# Microcontroller.net
KiCad netlist of a schematic drawn in Altium Designer
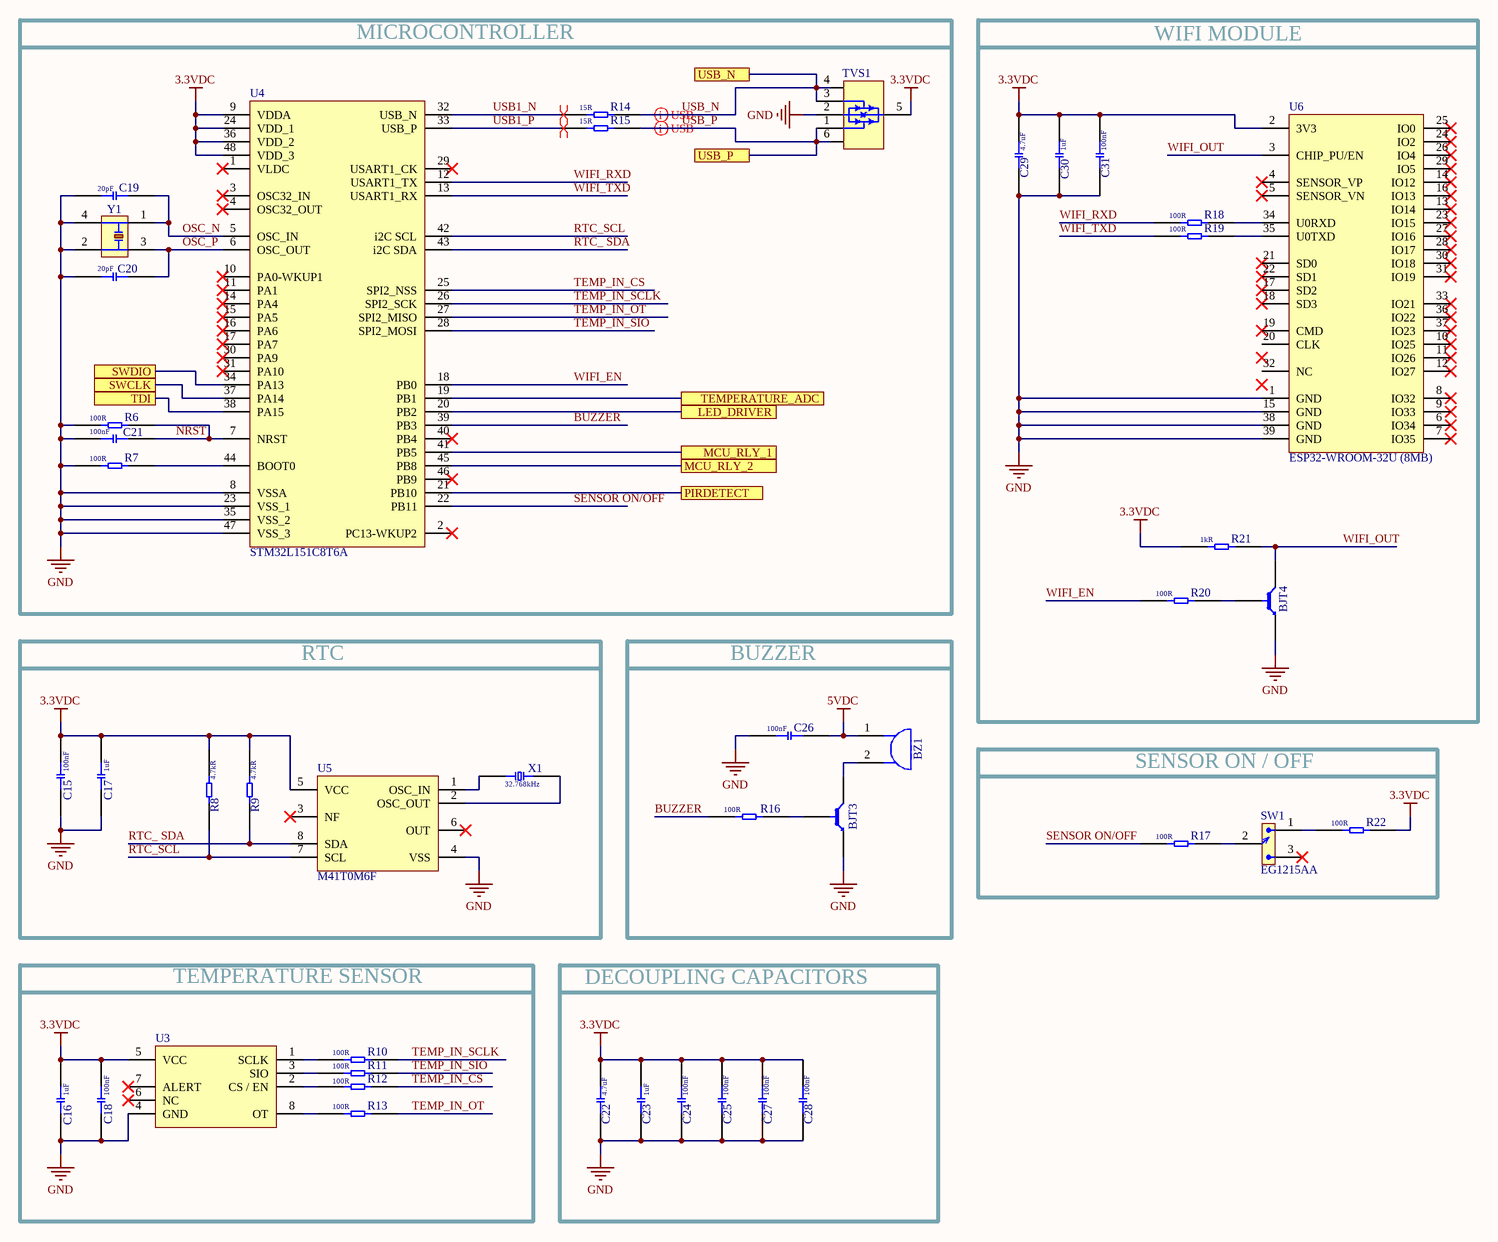
[diagram p0: Microcontroller.SchDoc]

(export (version "E")
  (design (tool "Eeschema 10.0.6"))
  (components
    (comp (ref "BJT3")
      (value "MMBT3904-7-F")
      (footprint "SOT-23F")
      (description "TRANS NPN 40V 0.2A SMD SOT23-3")
      (fields (field (name "MANUFACTURER") "Diodes Zetex") (field (name "DESIGNED BY") "M.C"))
      (libsource (lib "HedefPro_Library") (part "MMBT3904-7-F"))
    )
    (comp (ref "BJT4")
      (value "MMBT3904-7-F")
      (footprint "SOT-23F")
      (description "TRANS NPN 40V 0.2A SMD SOT23-3")
      (fields (field (name "MANUFACTURER") "Diodes Zetex") (field (name "DESIGNED BY") "M.C"))
      (libsource (lib "HedefPro_Library") (part "MMBT3904-7-F"))
    )
    (comp (ref "BZ1")
      (value "CMI-1295IC-0585T")
      (footprint "CMI-1295IC")
      (description "Buzzers Indicator, Internally Driven Magnetic 5 V 30mA 2.4kHz 85dB @ 5V, 10cm Through Hole PC Pins")
      (fields (field (name "MANUFACTURER") "CUI Devices") (field (name "DESIGNED BY") "M.C"))
      (libsource (lib "HedefPro_Library") (part "CMI-1295IC-0585T"))
    )
    (comp (ref "C15")
      (value "C0603C104K5RACTU")
      (footprint "CAP_0603")
      (description "Multilayer Ceramic Capacitors (MLCC) - SMD/SMT 50volts 0.1uF X7R 10%")
      (fields
        (field (name "MANUFACTURER") "KEMET")
        (field (name "TOLERANCE") "10%")
        (field (name "CAPACITANCE") "100nF")
        (field (name "DESIGNED BY") "M.C")
      )
      (libsource (lib "HedefPro_Library") (part "CAP 100nF 0603"))
    )
    (comp (ref "C16")
      (value "CL21B105KBFNNNE")
      (footprint "CAP_0805")
      (fields
        (field (name "MANUFACTURER") "Samsung")
        (field (name "TOLERANCE") "10%")
        (field (name "VOLTAGE") "50V")
        (field (name "CAPACITANCE") "1uF")
        (field (name "DESIGNED BY") "M.C")
      )
      (libsource (lib "HedefPro_Library") (part "CAP 1uF 0805"))
    )
    (comp (ref "C17")
      (value "CL21B105KBFNNNE")
      (footprint "CAP_0805")
      (fields
        (field (name "MANUFACTURER") "Samsung")
        (field (name "TOLERANCE") "10%")
        (field (name "VOLTAGE") "50V")
        (field (name "CAPACITANCE") "1uF")
        (field (name "DESIGNED BY") "M.C")
      )
      (libsource (lib "HedefPro_Library") (part "CAP 1uF 0805"))
    )
    (comp (ref "C18")
      (value "CL21B104KBCNNNC")
      (footprint "CAP_0805")
      (fields
        (field (name "MANUFACTURER") "Samsung")
        (field (name "TOLERANCE") "10%")
        (field (name "VOLTAGE") "50V")
        (field (name "CAPACITANCE") "100nF")
        (field (name "DESIGNED BY") "M.C")
      )
      (libsource (lib "HedefPro_Library") (part "CAP 100nF 0805"))
    )
    (comp (ref "C19")
      (value "CL10C200JB8NNNC")
      (footprint "CAP_0603")
      (fields
        (field (name "MANUFACTURER") "Samsung")
        (field (name "TOLERANCE") "5%")
        (field (name "VOLTAGE") "50V")
        (field (name "CAPACITANCE") "20pF")
        (field (name "DESIGNED BY") "M.C")
      )
      (libsource (lib "HedefPro_Library") (part "CAP 20pF 0805"))
    )
    (comp (ref "C20")
      (value "CL10C200JB8NNNC")
      (footprint "CAP_0603")
      (fields
        (field (name "MANUFACTURER") "Samsung")
        (field (name "TOLERANCE") "5%")
        (field (name "VOLTAGE") "50V")
        (field (name "CAPACITANCE") "20pF")
        (field (name "DESIGNED BY") "M.C")
      )
      (libsource (lib "HedefPro_Library") (part "CAP 20pF 0805"))
    )
    (comp (ref "C21")
      (value "CL21B104KBCNNNC")
      (footprint "CAP_0805")
      (fields
        (field (name "MANUFACTURER") "Samsung")
        (field (name "TOLERANCE") "10%")
        (field (name "VOLTAGE") "50V")
        (field (name "CAPACITANCE") "100nF")
        (field (name "DESIGNED BY") "M.C")
      )
      (libsource (lib "HedefPro_Library") (part "CAP 100nF 0805"))
    )
    (comp (ref "C22")
      (value "CL21A475KAQNNNE")
      (footprint "CAP_0805")
      (fields
        (field (name "MANUFACTURER") "Samsung")
        (field (name "TOLERANCE") "10%")
        (field (name "CAPACITANCE") "4.7uF")
        (field (name "DESIGNED BY") "M.C")
      )
      (libsource (lib "HedefPro_Library") (part "CAP 4.7uF 0805"))
    )
    (comp (ref "C23")
      (value "CL21B105KBFNNNE")
      (footprint "CAP_0805")
      (fields
        (field (name "MANUFACTURER") "Samsung")
        (field (name "TOLERANCE") "10%")
        (field (name "VOLTAGE") "50V")
        (field (name "CAPACITANCE") "1uF")
        (field (name "DESIGNED BY") "M.C")
      )
      (libsource (lib "HedefPro_Library") (part "CAP 1uF 0805"))
    )
    (comp (ref "C24")
      (value "CL21B104KBCNNNC")
      (footprint "CAP_0805")
      (fields
        (field (name "MANUFACTURER") "Samsung")
        (field (name "TOLERANCE") "10%")
        (field (name "VOLTAGE") "50V")
        (field (name "CAPACITANCE") "100nF")
        (field (name "DESIGNED BY") "M.C")
      )
      (libsource (lib "HedefPro_Library") (part "CAP 100nF 0805"))
    )
    (comp (ref "C25")
      (value "CL21B104KBCNNNC")
      (footprint "CAP_0805")
      (fields
        (field (name "MANUFACTURER") "Samsung")
        (field (name "TOLERANCE") "10%")
        (field (name "VOLTAGE") "50V")
        (field (name "CAPACITANCE") "100nF")
        (field (name "DESIGNED BY") "M.C")
      )
      (libsource (lib "HedefPro_Library") (part "CAP 100nF 0805"))
    )
    (comp (ref "C26")
      (value "ALA7DF471CF450")
      (footprint "CAP_0603")
      (description "CAP CER 100nF %10 0603 SMD")
      (fields
        (field (name "MANUFACTURER") "KEMET")
        (field (name "CAPATICANTE") "100nF")
        (field (name "DESIGNED BY") "M.C")
      )
      (libsource (lib "HedefPro_Library") (part "CAP 100nf 0603_1"))
    )
    (comp (ref "C27")
      (value "CL21B104KBCNNNC")
      (footprint "CAP_0805")
      (fields
        (field (name "MANUFACTURER") "Samsung")
        (field (name "TOLERANCE") "10%")
        (field (name "VOLTAGE") "50V")
        (field (name "CAPACITANCE") "100nF")
        (field (name "DESIGNED BY") "M.C")
      )
      (libsource (lib "HedefPro_Library") (part "CAP 100nF 0805"))
    )
    (comp (ref "C28")
      (value "CL21B104KBCNNNC")
      (footprint "CAP_0805")
      (fields
        (field (name "MANUFACTURER") "Samsung")
        (field (name "TOLERANCE") "10%")
        (field (name "VOLTAGE") "50V")
        (field (name "CAPACITANCE") "100nF")
        (field (name "DESIGNED BY") "M.C")
      )
      (libsource (lib "HedefPro_Library") (part "CAP 100nF 0805"))
    )
    (comp (ref "C29")
      (value "CL21A475KAQNNNE")
      (footprint "CAP_0805")
      (fields
        (field (name "MANUFACTURER") "Samsung")
        (field (name "TOLERANCE") "10%")
        (field (name "CAPACITANCE") "4.7uF")
        (field (name "DESIGNED BY") "M.C")
      )
      (libsource (lib "HedefPro_Library") (part "CAP 4.7uF 0805"))
    )
    (comp (ref "C30")
      (value "CL21B105KBFNNNE")
      (footprint "CAP_0805")
      (fields
        (field (name "MANUFACTURER") "Samsung")
        (field (name "TOLERANCE") "10%")
        (field (name "VOLTAGE") "50V")
        (field (name "CAPACITANCE") "1uF")
        (field (name "DESIGNED BY") "M.C")
      )
      (libsource (lib "HedefPro_Library") (part "CAP 1uF 0805"))
    )
    (comp (ref "C31")
      (value "CL21B104KBCNNNC")
      (footprint "CAP_0805")
      (fields
        (field (name "MANUFACTURER") "Samsung")
        (field (name "TOLERANCE") "10%")
        (field (name "VOLTAGE") "50V")
        (field (name "CAPACITANCE") "100nF")
        (field (name "DESIGNED BY") "M.C")
      )
      (libsource (lib "HedefPro_Library") (part "CAP 100nF 0805"))
    )
    (comp (ref "R6")
      (value "RC0603JR-07100RL")
      (footprint "RES_0603")
      (description "Res Thick Film 0603 100 Ohm 5% 0.1W(1/10W) ±100ppm/C Molded SMD Paper T/R")
      (fields
        (field (name "MANUFACTURER") "Yageo")
        (field (name "TOLERANCE") "5%")
        (field (name "RESISTANCE") "100R")
        (field (name "DESIGNED BY") "M.C")
      )
      (libsource (lib "HedefPro_Library") (part "RES 100R OHM 0603"))
    )
    (comp (ref "R7")
      (value "RC0603JR-07100RL")
      (footprint "RES_0603")
      (description "Res Thick Film 0603 100 Ohm 5% 0.1W(1/10W) ±100ppm/C Molded SMD Paper T/R")
      (fields
        (field (name "MANUFACTURER") "Yageo")
        (field (name "TOLERANCE") "5%")
        (field (name "RESISTANCE") "100R")
        (field (name "DESIGNED BY") "M.C")
      )
      (libsource (lib "HedefPro_Library") (part "RES 100R OHM 0603"))
    )
    (comp (ref "R8")
      (value "RC0603JR-074K7L")
      (footprint "RES_0603")
      (description "Res Thick Film 0603 4.7K Ohm 5% 0.1W(1/10W) ±100ppm/C Molded SMD Paper T/R")
      (fields
        (field (name "MANUFACTURER") "Yageo")
        (field (name "TOLERANCE") "5%")
        (field (name "RESISTANCE") "4.7kR")
        (field (name "DESIGNED BY") "M.C")
      )
      (libsource (lib "HedefPro_Library") (part "RES 4.7kR OHM 0603"))
    )
    (comp (ref "R9")
      (value "RC0603JR-074K7L")
      (footprint "RES_0603")
      (description "Res Thick Film 0603 4.7K Ohm 5% 0.1W(1/10W) ±100ppm/C Molded SMD Paper T/R")
      (fields
        (field (name "MANUFACTURER") "Yageo")
        (field (name "TOLERANCE") "5%")
        (field (name "RESISTANCE") "4.7kR")
        (field (name "DESIGNED BY") "M.C")
      )
      (libsource (lib "HedefPro_Library") (part "RES 4.7kR OHM 0603"))
    )
    (comp (ref "R10")
      (value "RC0603JR-07100RL")
      (footprint "RES_0603")
      (description "Res Thick Film 0603 100 Ohm 5% 0.1W(1/10W) ±100ppm/C Molded SMD Paper T/R")
      (fields
        (field (name "MANUFACTURER") "Yageo")
        (field (name "TOLERANCE") "5%")
        (field (name "RESISTANCE") "100R")
        (field (name "DESIGNED BY") "M.C")
      )
      (libsource (lib "HedefPro_Library") (part "RES 100R OHM 0603"))
    )
    (comp (ref "R11")
      (value "RC0603JR-07100RL")
      (footprint "RES_0603")
      (description "Res Thick Film 0603 100 Ohm 5% 0.1W(1/10W) ±100ppm/C Molded SMD Paper T/R")
      (fields
        (field (name "MANUFACTURER") "Yageo")
        (field (name "TOLERANCE") "5%")
        (field (name "RESISTANCE") "100R")
        (field (name "DESIGNED BY") "M.C")
      )
      (libsource (lib "HedefPro_Library") (part "RES 100R OHM 0603"))
    )
    (comp (ref "R12")
      (value "RC0603JR-07100RL")
      (footprint "RES_0603")
      (description "Res Thick Film 0603 100 Ohm 5% 0.1W(1/10W) ±100ppm/C Molded SMD Paper T/R")
      (fields
        (field (name "MANUFACTURER") "Yageo")
        (field (name "TOLERANCE") "5%")
        (field (name "RESISTANCE") "100R")
        (field (name "DESIGNED BY") "M.C")
      )
      (libsource (lib "HedefPro_Library") (part "RES 100R OHM 0603"))
    )
    (comp (ref "R13")
      (value "RC0603JR-07100RL")
      (footprint "RES_0603")
      (description "Res Thick Film 0603 100 Ohm 5% 0.1W(1/10W) ±100ppm/C Molded SMD Paper T/R")
      (fields
        (field (name "MANUFACTURER") "Yageo")
        (field (name "TOLERANCE") "5%")
        (field (name "RESISTANCE") "100R")
        (field (name "DESIGNED BY") "M.C")
      )
      (libsource (lib "HedefPro_Library") (part "RES 100R OHM 0603"))
    )
    (comp (ref "R14")
      (value "RC0603JR-0715RL")
      (footprint "RES_0603")
      (fields
        (field (name "MANUFACTURER") "Yageo")
        (field (name "TOLERANCE") "5%")
        (field (name "RESISTANCE") "15R")
        (field (name "DESIGNED BY") "M.C")
      )
      (libsource (lib "HedefPro_Library") (part "RES 15R OHM 0603"))
    )
    (comp (ref "R15")
      (value "RC0603JR-0715RL")
      (footprint "RES_0603")
      (fields
        (field (name "MANUFACTURER") "Yageo")
        (field (name "TOLERANCE") "5%")
        (field (name "RESISTANCE") "15R")
        (field (name "DESIGNED BY") "M.C")
      )
      (libsource (lib "HedefPro_Library") (part "RES 15R OHM 0603"))
    )
    (comp (ref "R16")
      (value "RC0603JR-07100RL")
      (footprint "RES_0603")
      (description "Res Thick Film 0603 100 Ohm 5% 0.1W(1/10W) ±100ppm/C Molded SMD Paper T/R")
      (fields
        (field (name "MANUFACTURER") "Yageo")
        (field (name "TOLERANCE") "5%")
        (field (name "RESISTANCE") "100R")
        (field (name "DESIGNED BY") "M.C")
      )
      (libsource (lib "HedefPro_Library") (part "RES 100R OHM 0603"))
    )
    (comp (ref "R17")
      (value "RC0603JR-07100RL")
      (footprint "RES_0603")
      (description "Res Thick Film 0603 100 Ohm 5% 0.1W(1/10W) ±100ppm/C Molded SMD Paper T/R")
      (fields
        (field (name "MANUFACTURER") "Yageo")
        (field (name "TOLERANCE") "5%")
        (field (name "RESISTANCE") "100R")
        (field (name "DESIGNED BY") "M.C")
      )
      (libsource (lib "HedefPro_Library") (part "RES 100R OHM 0603"))
    )
    (comp (ref "R18")
      (value "RC0603JR-07100RL")
      (footprint "RES_0603")
      (description "Res Thick Film 0603 100 Ohm 5% 0.1W(1/10W) ±100ppm/C Molded SMD Paper T/R")
      (fields
        (field (name "MANUFACTURER") "Yageo")
        (field (name "TOLERANCE") "5%")
        (field (name "RESISTANCE") "100R")
        (field (name "DESIGNED BY") "M.C")
      )
      (libsource (lib "HedefPro_Library") (part "RES 100R OHM 0603"))
    )
    (comp (ref "R19")
      (value "RC0603JR-07100RL")
      (footprint "RES_0603")
      (description "Res Thick Film 0603 100 Ohm 5% 0.1W(1/10W) ±100ppm/C Molded SMD Paper T/R")
      (fields
        (field (name "MANUFACTURER") "Yageo")
        (field (name "TOLERANCE") "5%")
        (field (name "RESISTANCE") "100R")
        (field (name "DESIGNED BY") "M.C")
      )
      (libsource (lib "HedefPro_Library") (part "RES 100R OHM 0603"))
    )
    (comp (ref "R20")
      (value "RC0603JR-07100RL")
      (footprint "RES_0603")
      (description "Res Thick Film 0603 100 Ohm 5% 0.1W(1/10W) ±100ppm/C Molded SMD Paper T/R")
      (fields
        (field (name "MANUFACTURER") "Yageo")
        (field (name "TOLERANCE") "5%")
        (field (name "RESISTANCE") "100R")
        (field (name "DESIGNED BY") "M.C")
      )
      (libsource (lib "HedefPro_Library") (part "RES 100R OHM 0603"))
    )
    (comp (ref "R21")
      (value "RC0603FR-101KL")
      (footprint "RES_0603")
      (description "Res Thick Film 0603 1K Ohm 1% 0.1W(1/10W) ±100ppm/C Pad SMD T/R")
      (fields
        (field (name "MANUFACTURER") "Yageo")
        (field (name "TOLERANCE") "1%")
        (field (name "RESISTANCE") "1kR")
        (field (name "DESIGNED BY") "M.C")
      )
      (libsource (lib "HedefPro_Library") (part "RES 1kR OHM 0603"))
    )
    (comp (ref "R22")
      (value "RC0603JR-07100RL")
      (footprint "RES_0603")
      (description "Res Thick Film 0603 100 Ohm 5% 0.1W(1/10W) ±100ppm/C Molded SMD Paper T/R")
      (fields
        (field (name "MANUFACTURER") "Yageo")
        (field (name "TOLERANCE") "5%")
        (field (name "RESISTANCE") "100R")
        (field (name "DESIGNED BY") "M.C")
      )
      (libsource (lib "HedefPro_Library") (part "RES 100R OHM 0603"))
    )
    (comp (ref "SW1")
      (value "EG1215AA")
      (footprint "EG1215AA")
      (description "Slide Switch, SPDT, 0.025A, 24V, SMD")
      (fields
        (field (name "MANUFACTURER") "E-Switch")
        (field (name "TOLERANCE") "4.95%")
        (field (name "DESIGNED BY") "M.C")
      )
      (libsource (lib "HedefPro_Library") (part "EG1215AA"))
    )
    (comp (ref "TVS1")
      (value "USBLC6-2SC6")
      (footprint "SOT23-6L")
      (description "TVS DIODE 5.25V 17V SOT23-6")
      (fields (field (name "MANUFACTURER") "STMicroelectronics") (field (name "DESIGNED BY") "M.C"))
      (libsource (lib "HedefPro_Library") (part "USBLC6-2SC6"))
    )
    (comp (ref "U3")
      (value "MAX6662MSA+T")
      (footprint "SOIC8")
      (description "Temp Sensor Digital Serial (3-Wire, SPI) 8-Pin SOIC N T/R")
      (fields (field (name "MANUFACTURER") "Maxim") (field (name "DESIGNED BY") "M.C"))
      (libsource (lib "HedefPro_Library") (part "MAX6662MSA+T"))
    )
    (comp (ref "U4")
      (value "STM32L151C8T6A")
      (footprint "LQFP48")
      (description "IC MCU 32BIT 64KB FLASH 48LQFP")
      (fields (field (name "MANUFACTURER") "STMicroelectronics") (field (name "DESIGNED BY") "M.C"))
      (libsource (lib "HedefPro_Library") (part "STM32L151C8T6A"))
    )
    (comp (ref "U5")
      (value "M41T0M6F")
      (footprint "SOIC8")
      (description "Real Time Clock Serial 8Byte 8-Pin SO N T/R")
      (fields (field (name "MANUFACTURER") "STMicroelectronics") (field (name "DESIGNED BY") "M.C"))
      (libsource (lib "HedefPro_Library") (part "M41T0M6F"))
    )
    (comp (ref "U6")
      (value "ESP32-WROOM-32U (8MB)")
      (footprint "ESP32_32U")
      (description "SMD Module, ESP32-D0WD, 64MBITS Spi Flash, Uart Mode, U.fl Antenna Connector")
      (fields
        (field (name "MANUFACTURER") "Espressif Systems")
        (field (name "TOLERANCE") "0.1%")
        (field (name "DESIGNED BY") "M.C")
      )
      (libsource (lib "HedefPro_Library") (part "ESP32-WROOM-32U (8MB)"))
    )
    (comp (ref "X1")
      (value "ABS05-32.768KHZ-T")
      (footprint "ABS05")
      (description "ABRACON - ABS05-32.768KHZ-T - Crystal, 32.768 kHz, SMD, 1.6mm x 1mm, 12.5 pF, 20 ppm, ABS05 Series")
      (fields
        (field (name "MANUFACTURER") "Abracon")
        (field (name "TOLERANCE") "20ppm")
        (field (name "FREQUENCY") "32.768kHz")
        (field (name "DESIGNED BY") "M.C")
      )
      (libsource (lib "HedefPro_Library") (part "ABS05-32.768KHZ-T"))
    )
    (comp (ref "Y1")
      (value "ECS-160-20-30B-TR")
      (footprint "SMD5032")
      (description "CRYSTAL 16.0000MHZ 20PF SMD")
      (fields
        (field (name "MANUFACTURER") "ECS International")
        (field (name "TOLERANCE") "50ppm")
        (field (name "DESIGNED BY") "M.C")
      )
      (libsource (lib "HedefPro_Library") (part "ECS-160-20-30B-TR"))
    )
  )
  (nets
    (net (code "1") (name "/BUZZER") (class "Default")
      (node (ref "R16") (pin "1") (pinfunction "1_1") (pintype "passive"))
      (node (ref "U4") (pin "39") (pinfunction "PB3_39") (pintype "passive"))
    )
    (net (code "2") (name "/LED_DRIVER") (class "Default")
      (node (ref "U4") (pin "20") (pinfunction "PB2_20") (pintype "passive"))
    )
    (net (code "3") (name "/MCU_RLY_1") (class "Default")
      (node (ref "U4") (pin "41") (pinfunction "PB5_41") (pintype "passive"))
    )
    (net (code "4") (name "/MCU_RLY_2") (class "Default")
      (node (ref "U4") (pin "45") (pinfunction "PB8_45") (pintype "passive"))
    )
    (net (code "5") (name "/NRST") (class "Default")
      (node (ref "C21") (pin "1") (pinfunction "1_1") (pintype "passive"))
      (node (ref "R6") (pin "2") (pinfunction "2_2") (pintype "passive"))
      (node (ref "U4") (pin "7") (pinfunction "NRST_7") (pintype "passive"))
    )
    (net (code "6") (name "/OSC_N") (class "Default")
      (node (ref "C19") (pin "2") (pinfunction "2_2") (pintype "passive"))
      (node (ref "U4") (pin "5") (pinfunction "OSC_IN_5") (pintype "passive"))
      (node (ref "Y1") (pin "1") (pinfunction "IN/OUT_1") (pintype "passive"))
    )
    (net (code "7") (name "/OSC_P") (class "Default")
      (node (ref "C20") (pin "2") (pinfunction "2_2") (pintype "passive"))
      (node (ref "U4") (pin "6") (pinfunction "OSC_OUT_6") (pintype "passive"))
      (node (ref "Y1") (pin "3") (pinfunction "OUT/IN_3") (pintype "passive"))
    )
    (net (code "8") (name "/PIRDETECT") (class "Default")
      (node (ref "U4") (pin "21") (pinfunction "PB10_21") (pintype "passive"))
    )
    (net (code "9") (name "/RTC_ SDA") (class "Default")
      (node (ref "R9") (pin "1") (pinfunction "1_1") (pintype "passive"))
      (node (ref "U4") (pin "43") (pinfunction "i2C_SDA_43") (pintype "passive"))
      (node (ref "U5") (pin "8") (pinfunction "SDA_8") (pintype "passive"))
    )
    (net (code "10") (name "/RTC_SCL") (class "Default")
      (node (ref "R8") (pin "1") (pinfunction "1_1") (pintype "passive"))
      (node (ref "U4") (pin "42") (pinfunction "i2C_SCL_42") (pintype "passive"))
      (node (ref "U5") (pin "7") (pinfunction "SCL_7") (pintype "passive"))
    )
    (net (code "11") (name "/SENSOR ON{slash}OFF") (class "Default")
      (node (ref "R17") (pin "1") (pinfunction "1_1") (pintype "passive"))
      (node (ref "U4") (pin "22") (pinfunction "PB11_22") (pintype "passive"))
    )
    (net (code "12") (name "/SWCLK") (class "Default")
      (node (ref "U4") (pin "37") (pinfunction "PA14_37") (pintype "passive"))
    )
    (net (code "13") (name "/SWDIO") (class "Default")
      (node (ref "U4") (pin "34") (pinfunction "PA13_34") (pintype "passive"))
    )
    (net (code "14") (name "/TDI") (class "Default")
      (node (ref "U4") (pin "38") (pinfunction "PA15_38") (pintype "passive"))
    )
    (net (code "15") (name "/TEMPERATURE_ADC") (class "Default")
      (node (ref "U4") (pin "19") (pinfunction "PB1_19") (pintype "passive"))
    )
    (net (code "16") (name "/TEMP_IN_CS") (class "Default")
      (node (ref "R12") (pin "1") (pinfunction "1_1") (pintype "passive"))
      (node (ref "U4") (pin "25") (pinfunction "SPI2_NSS_25") (pintype "passive"))
    )
    (net (code "17") (name "/TEMP_IN_OT") (class "Default")
      (node (ref "R13") (pin "1") (pinfunction "1_1") (pintype "passive"))
      (node (ref "U4") (pin "27") (pinfunction "SPI2_MISO_27") (pintype "passive"))
    )
    (net (code "18") (name "/TEMP_IN_SCLK") (class "Default")
      (node (ref "R10") (pin "1") (pinfunction "1_1") (pintype "passive"))
      (node (ref "U4") (pin "26") (pinfunction "SPI2_SCK_26") (pintype "passive"))
    )
    (net (code "19") (name "/TEMP_IN_SIO") (class "Default")
      (node (ref "R11") (pin "1") (pinfunction "1_1") (pintype "passive"))
      (node (ref "U4") (pin "28") (pinfunction "SPI2_MOSI_28") (pintype "passive"))
    )
    (net (code "20") (name "/USB1_N") (class "Default")
      (node (ref "R14") (pin "1") (pinfunction "1_1") (pintype "passive"))
      (node (ref "U4") (pin "32") (pinfunction "USB_N_32") (pintype "passive"))
    )
    (net (code "21") (name "/USB1_P") (class "Default")
      (node (ref "R15") (pin "1") (pinfunction "1_1") (pintype "passive"))
      (node (ref "U4") (pin "33") (pinfunction "USB_P_33") (pintype "passive"))
    )
    (net (code "22") (name "/USB_N") (class "Default")
      (node (ref "R14") (pin "2") (pinfunction "2_2") (pintype "passive"))
      (node (ref "TVS1") (pin "3") (pinfunction "D+in_3") (pintype "passive"))
      (node (ref "TVS1") (pin "4") (pinfunction "D+out_4") (pintype "passive"))
    )
    (net (code "23") (name "/USB_P") (class "Default")
      (node (ref "R15") (pin "2") (pinfunction "2_2") (pintype "passive"))
      (node (ref "TVS1") (pin "1") (pinfunction "D+in_1") (pintype "passive"))
      (node (ref "TVS1") (pin "6") (pinfunction "D-out_6") (pintype "passive"))
    )
    (net (code "24") (name "/WIFI_EN") (class "Default")
      (node (ref "R20") (pin "1") (pinfunction "1_1") (pintype "passive"))
      (node (ref "U4") (pin "18") (pinfunction "PB0_18") (pintype "passive"))
    )
    (net (code "25") (name "/WIFI_OUT") (class "Default")
      (node (ref "BJT4") (pin "3") (pinfunction "C_3") (pintype "passive"))
      (node (ref "R21") (pin "2") (pinfunction "2_2") (pintype "passive"))
      (node (ref "U6") (pin "3") (pinfunction "CHIP_PU/EN_3") (pintype "passive"))
    )
    (net (code "26") (name "/WIFI_RXD") (class "Default")
      (node (ref "R18") (pin "2") (pinfunction "2_2") (pintype "passive"))
      (node (ref "U4") (pin "12") (pinfunction "USART1_TX_12") (pintype "passive"))
    )
    (net (code "27") (name "/WIFI_TXD") (class "Default")
      (node (ref "R19") (pin "2") (pinfunction "2_2") (pintype "passive"))
      (node (ref "U4") (pin "13") (pinfunction "USART1_RX_13") (pintype "passive"))
    )
    (net (code "28") (name "3.3VDC") (class "Default")
      (node (ref "C15") (pin "2") (pinfunction "2_2") (pintype "passive"))
      (node (ref "C16") (pin "2") (pinfunction "2_2") (pintype "passive"))
      (node (ref "C17") (pin "2") (pinfunction "2_2") (pintype "passive"))
      (node (ref "C18") (pin "2") (pinfunction "2_2") (pintype "passive"))
      (node (ref "C22") (pin "2") (pinfunction "2_2") (pintype "passive"))
      (node (ref "C23") (pin "2") (pinfunction "2_2") (pintype "passive"))
      (node (ref "C24") (pin "2") (pinfunction "2_2") (pintype "passive"))
      (node (ref "C25") (pin "2") (pinfunction "2_2") (pintype "passive"))
      (node (ref "C27") (pin "2") (pinfunction "2_2") (pintype "passive"))
      (node (ref "C28") (pin "2") (pinfunction "2_2") (pintype "passive"))
      (node (ref "C29") (pin "2") (pinfunction "2_2") (pintype "passive"))
      (node (ref "C30") (pin "2") (pinfunction "2_2") (pintype "passive"))
      (node (ref "C31") (pin "2") (pinfunction "2_2") (pintype "passive"))
      (node (ref "R21") (pin "1") (pinfunction "1_1") (pintype "passive"))
      (node (ref "R22") (pin "2") (pinfunction "2_2") (pintype "passive"))
      (node (ref "R8") (pin "2") (pinfunction "2_2") (pintype "passive"))
      (node (ref "R9") (pin "2") (pinfunction "2_2") (pintype "passive"))
      (node (ref "TVS1") (pin "5") (pinfunction "VBUS_5") (pintype "passive"))
      (node (ref "U3") (pin "5") (pinfunction "VCC_5") (pintype "passive"))
      (node (ref "U4") (pin "24") (pinfunction "VDD_1_24") (pintype "passive"))
      (node (ref "U4") (pin "36") (pinfunction "VDD_2_36") (pintype "passive"))
      (node (ref "U4") (pin "48") (pinfunction "VDD_3_48") (pintype "passive"))
      (node (ref "U4") (pin "9") (pinfunction "VDDA_9") (pintype "passive"))
      (node (ref "U5") (pin "5") (pinfunction "VCC_5") (pintype "passive"))
      (node (ref "U6") (pin "2") (pinfunction "3V3_2") (pintype "passive"))
    )
    (net (code "29") (name "5VDC") (class "Default")
      (node (ref "BZ1") (pin "1") (pinfunction "1_1") (pintype "passive"))
      (node (ref "C26") (pin "2") (pinfunction "2_2") (pintype "passive"))
    )
    (net (code "30") (name "GND") (class "Default")
      (node (ref "BJT3") (pin "2") (pinfunction "E_2") (pintype "passive"))
      (node (ref "BJT4") (pin "2") (pinfunction "E_2") (pintype "passive"))
      (node (ref "C15") (pin "1") (pinfunction "1_1") (pintype "passive"))
      (node (ref "C16") (pin "1") (pinfunction "1_1") (pintype "passive"))
      (node (ref "C17") (pin "1") (pinfunction "1_1") (pintype "passive"))
      (node (ref "C18") (pin "1") (pinfunction "1_1") (pintype "passive"))
      (node (ref "C19") (pin "1") (pinfunction "1_1") (pintype "passive"))
      (node (ref "C20") (pin "1") (pinfunction "1_1") (pintype "passive"))
      (node (ref "C21") (pin "2") (pinfunction "2_2") (pintype "passive"))
      (node (ref "C22") (pin "1") (pinfunction "1_1") (pintype "passive"))
      (node (ref "C23") (pin "1") (pinfunction "1_1") (pintype "passive"))
      (node (ref "C24") (pin "1") (pinfunction "1_1") (pintype "passive"))
      (node (ref "C25") (pin "1") (pinfunction "1_1") (pintype "passive"))
      (node (ref "C26") (pin "1") (pinfunction "1_1") (pintype "passive"))
      (node (ref "C27") (pin "1") (pinfunction "1_1") (pintype "passive"))
      (node (ref "C28") (pin "1") (pinfunction "1_1") (pintype "passive"))
      (node (ref "C29") (pin "1") (pinfunction "1_1") (pintype "passive"))
      (node (ref "C30") (pin "1") (pinfunction "1_1") (pintype "passive"))
      (node (ref "C31") (pin "1") (pinfunction "1_1") (pintype "passive"))
      (node (ref "R6") (pin "1") (pinfunction "1_1") (pintype "passive"))
      (node (ref "R7") (pin "1") (pinfunction "1_1") (pintype "passive"))
      (node (ref "TVS1") (pin "2") (pinfunction "GND_2") (pintype "passive"))
      (node (ref "U3") (pin "4") (pinfunction "GND_4") (pintype "passive"))
      (node (ref "U4") (pin "23") (pinfunction "VSS_1_23") (pintype "passive"))
      (node (ref "U4") (pin "35") (pinfunction "VSS_2_35") (pintype "passive"))
      (node (ref "U4") (pin "47") (pinfunction "VSS_3_47") (pintype "passive"))
      (node (ref "U4") (pin "8") (pinfunction "VSSA_8") (pintype "passive"))
      (node (ref "U5") (pin "4") (pinfunction "VSS_4") (pintype "passive"))
      (node (ref "U6") (pin "1") (pinfunction "GND_1") (pintype "passive"))
      (node (ref "U6") (pin "15") (pinfunction "GND_15") (pintype "passive"))
      (node (ref "U6") (pin "38") (pinfunction "GND_38") (pintype "passive"))
      (node (ref "U6") (pin "39") (pinfunction "GND_39") (pintype "passive"))
      (node (ref "Y1") (pin "2") (pinfunction "GND_2") (pintype "passive"))
      (node (ref "Y1") (pin "4") (pinfunction "GND_4") (pintype "passive"))
    )
    (net (code "31") (name "Net-(BJT3-B)") (class "Default")
      (node (ref "BJT3") (pin "1") (pinfunction "B_1") (pintype "passive"))
      (node (ref "R16") (pin "2") (pinfunction "2_2") (pintype "passive"))
    )
    (net (code "32") (name "Net-(BJT3-C)") (class "Default")
      (node (ref "BJT3") (pin "3") (pinfunction "C_3") (pintype "passive"))
      (node (ref "BZ1") (pin "2") (pinfunction "2_2") (pintype "passive"))
    )
    (net (code "33") (name "Net-(BJT4-B)") (class "Default")
      (node (ref "BJT4") (pin "1") (pinfunction "B_1") (pintype "passive"))
      (node (ref "R20") (pin "2") (pinfunction "2_2") (pintype "passive"))
    )
    (net (code "34") (name "Net-(R22-Pad1)") (class "Default")
      (node (ref "R22") (pin "1") (pinfunction "1_1") (pintype "passive"))
      (node (ref "SW1") (pin "1") (pinfunction "1_1") (pintype "passive"))
    )
    (net (code "35") (name "Net-(SW1-Base)") (class "Default")
      (node (ref "R17") (pin "2") (pinfunction "2_2") (pintype "passive"))
      (node (ref "SW1") (pin "2") (pinfunction "Base_2") (pintype "passive"))
    )
    (net (code "36") (name "Net-(U3-CS_{slash}_EN)") (class "Default")
      (node (ref "R12") (pin "2") (pinfunction "2_2") (pintype "passive"))
      (node (ref "U3") (pin "2") (pinfunction "CS_/_EN_2") (pintype "passive"))
    )
    (net (code "37") (name "Net-(U3-OT)") (class "Default")
      (node (ref "R13") (pin "2") (pinfunction "2_2") (pintype "passive"))
      (node (ref "U3") (pin "8") (pinfunction "OT_8") (pintype "passive"))
    )
    (net (code "38") (name "Net-(U3-SCLK)") (class "Default")
      (node (ref "R10") (pin "2") (pinfunction "2_2") (pintype "passive"))
      (node (ref "U3") (pin "1") (pinfunction "SCLK_1") (pintype "passive"))
    )
    (net (code "39") (name "Net-(U3-SIO)") (class "Default")
      (node (ref "R11") (pin "2") (pinfunction "2_2") (pintype "passive"))
      (node (ref "U3") (pin "3") (pinfunction "SIO_3") (pintype "passive"))
    )
    (net (code "40") (name "Net-(U4-BOOT0)") (class "Default")
      (node (ref "R7") (pin "2") (pinfunction "2_2") (pintype "passive"))
      (node (ref "U4") (pin "44") (pinfunction "BOOT0_44") (pintype "passive"))
    )
    (net (code "41") (name "Net-(U5-OSC_IN)") (class "Default")
      (node (ref "U5") (pin "1") (pinfunction "OSC_IN_1") (pintype "passive"))
      (node (ref "X1") (pin "1") (pinfunction "1_1") (pintype "passive"))
    )
    (net (code "42") (name "Net-(U5-OSC_OUT)") (class "Default")
      (node (ref "U5") (pin "2") (pinfunction "OSC_OUT_2") (pintype "passive"))
      (node (ref "X1") (pin "2") (pinfunction "2_2") (pintype "passive"))
    )
    (net (code "43") (name "Net-(U6-U0RXD)") (class "Default")
      (node (ref "R18") (pin "1") (pinfunction "1_1") (pintype "passive"))
      (node (ref "U6") (pin "34") (pinfunction "U0RXD_34") (pintype "passive"))
    )
    (net (code "44") (name "Net-(U6-U0TXD)") (class "Default")
      (node (ref "R19") (pin "1") (pinfunction "1_1") (pintype "passive"))
      (node (ref "U6") (pin "35") (pinfunction "U0TXD_35") (pintype "passive"))
    )
    (net (code "45") (name "unconnected-(SW1-Pad3)") (class "Default")
      (node (ref "SW1") (pin "3") (pinfunction "3_3") (pintype "passive+no_connect"))
    )
    (net (code "46") (name "unconnected-(U3-ALERT-Pad7)") (class "Default")
      (node (ref "U3") (pin "7") (pinfunction "ALERT_7") (pintype "passive+no_connect"))
    )
    (net (code "47") (name "unconnected-(U3-NC-Pad6)") (class "Default")
      (node (ref "U3") (pin "6") (pinfunction "NC_6") (pintype "passive+no_connect"))
    )
    (net (code "48") (name "unconnected-(U4-OSC32_IN-Pad3)") (class "Default")
      (node (ref "U4") (pin "3") (pinfunction "OSC32_IN_3") (pintype "passive+no_connect"))
    )
    (net (code "49") (name "unconnected-(U4-OSC32_OUT-Pad4)") (class "Default")
      (node (ref "U4") (pin "4") (pinfunction "OSC32_OUT_4") (pintype "passive+no_connect"))
    )
    (net (code "50") (name "unconnected-(U4-PA0-WKUP1-Pad10)") (class "Default")
      (node (ref "U4") (pin "10") (pinfunction "PA0-WKUP1_10") (pintype "passive+no_connect"))
    )
    (net (code "51") (name "unconnected-(U4-PA1-Pad11)") (class "Default")
      (node (ref "U4") (pin "11") (pinfunction "PA1_11") (pintype "passive+no_connect"))
    )
    (net (code "52") (name "unconnected-(U4-PA4-Pad14)") (class "Default")
      (node (ref "U4") (pin "14") (pinfunction "PA4_14") (pintype "passive+no_connect"))
    )
    (net (code "53") (name "unconnected-(U4-PA5-Pad15)") (class "Default")
      (node (ref "U4") (pin "15") (pinfunction "PA5_15") (pintype "passive+no_connect"))
    )
    (net (code "54") (name "unconnected-(U4-PA6-Pad16)") (class "Default")
      (node (ref "U4") (pin "16") (pinfunction "PA6_16") (pintype "passive+no_connect"))
    )
    (net (code "55") (name "unconnected-(U4-PA7-Pad17)") (class "Default")
      (node (ref "U4") (pin "17") (pinfunction "PA7_17") (pintype "passive+no_connect"))
    )
    (net (code "56") (name "unconnected-(U4-PA9-Pad30)") (class "Default")
      (node (ref "U4") (pin "30") (pinfunction "PA9_30") (pintype "passive+no_connect"))
    )
    (net (code "57") (name "unconnected-(U4-PA10-Pad31)") (class "Default")
      (node (ref "U4") (pin "31") (pinfunction "PA10_31") (pintype "passive+no_connect"))
    )
    (net (code "58") (name "unconnected-(U4-PB4-Pad40)") (class "Default")
      (node (ref "U4") (pin "40") (pinfunction "PB4_40") (pintype "passive+no_connect"))
    )
    (net (code "59") (name "unconnected-(U4-PB9-Pad46)") (class "Default")
      (node (ref "U4") (pin "46") (pinfunction "PB9_46") (pintype "passive+no_connect"))
    )
    (net (code "60") (name "unconnected-(U4-PC13-WKUP2-Pad2)") (class "Default")
      (node (ref "U4") (pin "2") (pinfunction "PC13-WKUP2_2") (pintype "passive+no_connect"))
    )
    (net (code "61") (name "unconnected-(U4-USART1_CK-Pad29)") (class "Default")
      (node (ref "U4") (pin "29") (pinfunction "USART1_CK_29") (pintype "passive+no_connect"))
    )
    (net (code "62") (name "unconnected-(U4-VLDC-Pad1)") (class "Default")
      (node (ref "U4") (pin "1") (pinfunction "VLDC_1") (pintype "passive+no_connect"))
    )
    (net (code "63") (name "unconnected-(U5-NF-Pad3)") (class "Default")
      (node (ref "U5") (pin "3") (pinfunction "NF_3") (pintype "passive+no_connect"))
    )
    (net (code "64") (name "unconnected-(U5-OUT-Pad6)") (class "Default")
      (node (ref "U5") (pin "6") (pinfunction "OUT_6") (pintype "passive+no_connect"))
    )
    (net (code "65") (name "unconnected-(U6-CLK-Pad20)") (class "Default")
      (node (ref "U6") (pin "20") (pinfunction "CLK_20") (pintype "passive"))
    )
    (net (code "66") (name "unconnected-(U6-CMD-Pad19)") (class "Default")
      (node (ref "U6") (pin "19") (pinfunction "CMD_19") (pintype "passive+no_connect"))
    )
    (net (code "67") (name "unconnected-(U6-IO0-Pad25)") (class "Default")
      (node (ref "U6") (pin "25") (pinfunction "IO0_25") (pintype "passive+no_connect"))
    )
    (net (code "68") (name "unconnected-(U6-IO2-Pad24)") (class "Default")
      (node (ref "U6") (pin "24") (pinfunction "IO2_24") (pintype "passive+no_connect"))
    )
    (net (code "69") (name "unconnected-(U6-IO4-Pad26)") (class "Default")
      (node (ref "U6") (pin "26") (pinfunction "IO4_26") (pintype "passive+no_connect"))
    )
    (net (code "70") (name "unconnected-(U6-IO5-Pad29)") (class "Default")
      (node (ref "U6") (pin "29") (pinfunction "IO5_29") (pintype "passive+no_connect"))
    )
    (net (code "71") (name "unconnected-(U6-IO12-Pad14)") (class "Default")
      (node (ref "U6") (pin "14") (pinfunction "IO12_14") (pintype "passive+no_connect"))
    )
    (net (code "72") (name "unconnected-(U6-IO13-Pad16)") (class "Default")
      (node (ref "U6") (pin "16") (pinfunction "IO13_16") (pintype "passive+no_connect"))
    )
    (net (code "73") (name "unconnected-(U6-IO14-Pad13)") (class "Default")
      (node (ref "U6") (pin "13") (pinfunction "IO14_13") (pintype "passive+no_connect"))
    )
    (net (code "74") (name "unconnected-(U6-IO15-Pad23)") (class "Default")
      (node (ref "U6") (pin "23") (pinfunction "IO15_23") (pintype "passive+no_connect"))
    )
    (net (code "75") (name "unconnected-(U6-IO16-Pad27)") (class "Default")
      (node (ref "U6") (pin "27") (pinfunction "IO16_27") (pintype "passive+no_connect"))
    )
    (net (code "76") (name "unconnected-(U6-IO17-Pad28)") (class "Default")
      (node (ref "U6") (pin "28") (pinfunction "IO17_28") (pintype "passive+no_connect"))
    )
    (net (code "77") (name "unconnected-(U6-IO18-Pad30)") (class "Default")
      (node (ref "U6") (pin "30") (pinfunction "IO18_30") (pintype "passive+no_connect"))
    )
    (net (code "78") (name "unconnected-(U6-IO19-Pad31)") (class "Default")
      (node (ref "U6") (pin "31") (pinfunction "IO19_31") (pintype "passive+no_connect"))
    )
    (net (code "79") (name "unconnected-(U6-IO21-Pad33)") (class "Default")
      (node (ref "U6") (pin "33") (pinfunction "IO21_33") (pintype "passive+no_connect"))
    )
    (net (code "80") (name "unconnected-(U6-IO22-Pad36)") (class "Default")
      (node (ref "U6") (pin "36") (pinfunction "IO22_36") (pintype "passive+no_connect"))
    )
    (net (code "81") (name "unconnected-(U6-IO23-Pad37)") (class "Default")
      (node (ref "U6") (pin "37") (pinfunction "IO23_37") (pintype "passive+no_connect"))
    )
    (net (code "82") (name "unconnected-(U6-IO25-Pad10)") (class "Default")
      (node (ref "U6") (pin "10") (pinfunction "IO25_10") (pintype "passive+no_connect"))
    )
    (net (code "83") (name "unconnected-(U6-IO26-Pad11)") (class "Default")
      (node (ref "U6") (pin "11") (pinfunction "IO26_11") (pintype "passive+no_connect"))
    )
    (net (code "84") (name "unconnected-(U6-IO27-Pad12)") (class "Default")
      (node (ref "U6") (pin "12") (pinfunction "IO27_12") (pintype "passive+no_connect"))
    )
    (net (code "85") (name "unconnected-(U6-IO32-Pad8)") (class "Default")
      (node (ref "U6") (pin "8") (pinfunction "IO32_8") (pintype "passive+no_connect"))
    )
    (net (code "86") (name "unconnected-(U6-IO33-Pad9)") (class "Default")
      (node (ref "U6") (pin "9") (pinfunction "IO33_9") (pintype "passive+no_connect"))
    )
    (net (code "87") (name "unconnected-(U6-IO34-Pad6)") (class "Default")
      (node (ref "U6") (pin "6") (pinfunction "IO34_6") (pintype "passive+no_connect"))
    )
    (net (code "88") (name "unconnected-(U6-IO35-Pad7)") (class "Default")
      (node (ref "U6") (pin "7") (pinfunction "IO35_7") (pintype "passive+no_connect"))
    )
    (net (code "89") (name "unconnected-(U6-NC-Pad32)") (class "Default")
      (node (ref "U6") (pin "32") (pinfunction "NC_32") (pintype "passive"))
    )
    (net (code "90") (name "unconnected-(U6-SD0-Pad21)") (class "Default")
      (node (ref "U6") (pin "21") (pinfunction "SD0_21") (pintype "passive+no_connect"))
    )
    (net (code "91") (name "unconnected-(U6-SD1-Pad22)") (class "Default")
      (node (ref "U6") (pin "22") (pinfunction "SD1_22") (pintype "passive+no_connect"))
    )
    (net (code "92") (name "unconnected-(U6-SD2-Pad17)") (class "Default")
      (node (ref "U6") (pin "17") (pinfunction "SD2_17") (pintype "passive+no_connect"))
    )
    (net (code "93") (name "unconnected-(U6-SD3-Pad18)") (class "Default")
      (node (ref "U6") (pin "18") (pinfunction "SD3_18") (pintype "passive+no_connect"))
    )
    (net (code "94") (name "unconnected-(U6-SENSOR_VN-Pad5)") (class "Default")
      (node (ref "U6") (pin "5") (pinfunction "SENSOR_VN_5") (pintype "passive+no_connect"))
    )
    (net (code "95") (name "unconnected-(U6-SENSOR_VP-Pad4)") (class "Default")
      (node (ref "U6") (pin "4") (pinfunction "SENSOR_VP_4") (pintype "passive+no_connect"))
    )
  )
)
